# a78-flashcart.net
KiCad netlist of a schematic drawn in EAGLE
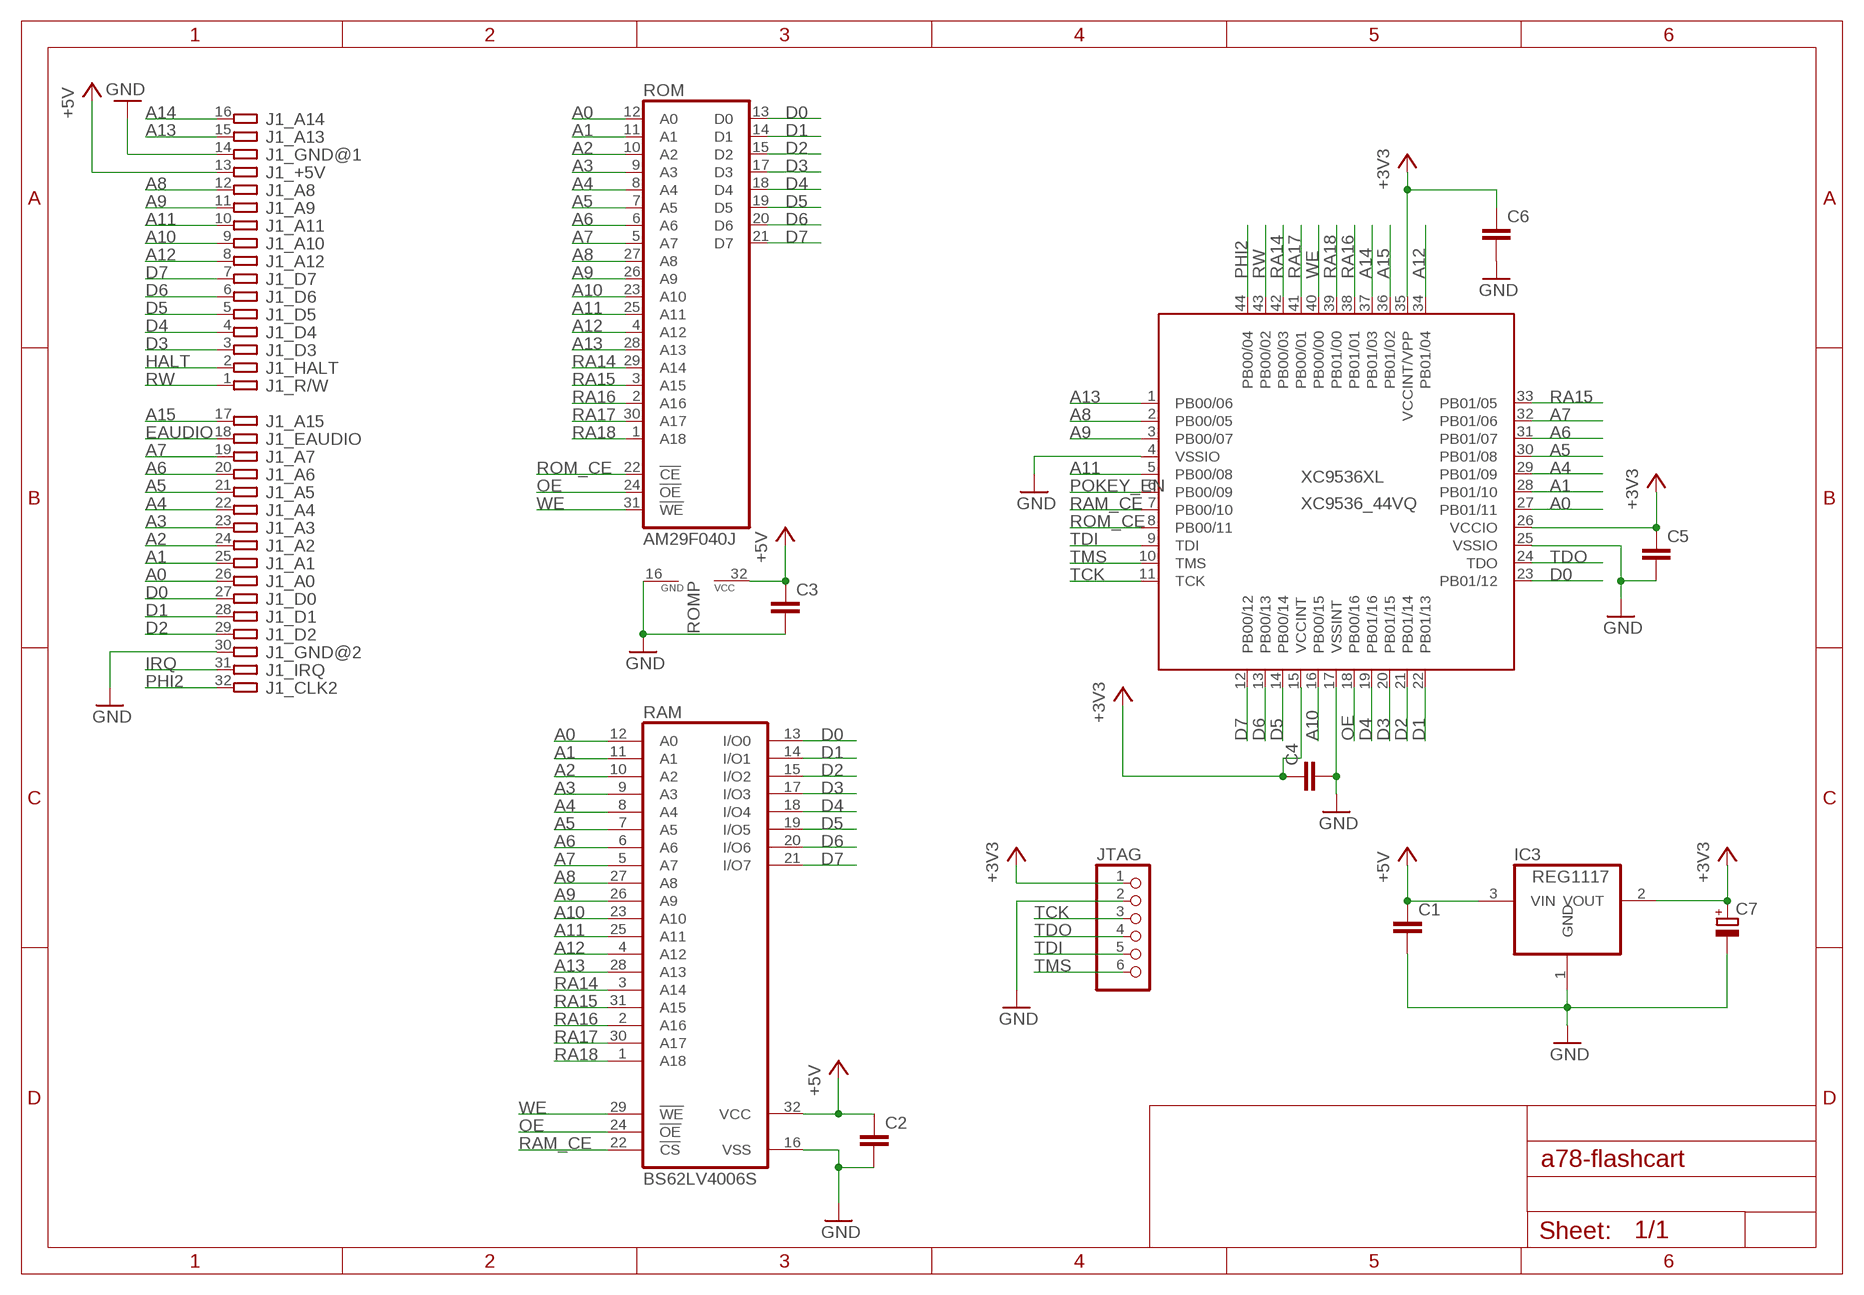
[diagram p0: schematic, sheet 1]

(export (version "E")
  (design (tool "Eeschema 10.0.6"))
  (components
    (comp (ref "C1")
      (value "C-EUC0603")
      (footprint "eagle-import:C0603")
      (libsource (lib "eagle-import") (part "C-EUC0603"))
    )
    (comp (ref "C2")
      (value "C-EUC0603")
      (footprint "eagle-import:C0603")
      (libsource (lib "eagle-import") (part "C-EUC0603"))
    )
    (comp (ref "C3")
      (value "C-EUC0603")
      (footprint "eagle-import:C0603")
      (libsource (lib "eagle-import") (part "C-EUC0603"))
    )
    (comp (ref "C4")
      (value "C-EUC0603")
      (footprint "eagle-import:C0603")
      (libsource (lib "eagle-import") (part "C-EUC0603"))
    )
    (comp (ref "C5")
      (value "C-EUC0603")
      (footprint "eagle-import:C0603")
      (libsource (lib "eagle-import") (part "C-EUC0603"))
    )
    (comp (ref "C6")
      (value "C-EUC0603")
      (footprint "eagle-import:C0603")
      (libsource (lib "eagle-import") (part "C-EUC0603"))
    )
    (comp (ref "C7")
      (value "CPOL-EUSMCC")
      (footprint "eagle-import:SMC_C")
      (libsource (lib "eagle-import") (part "CPOL-EUSMCC"))
    )
    (comp (ref "IC3")
      (value "REG1117")
      (footprint "eagle-import:SOT223")
      (libsource (lib "eagle-import") (part "REG1117"))
    )
    (comp (ref "J1")
      (value "ATARI-7800-SMALL")
      (footprint "eagle-import:ATARI-7800-SMALL")
      (libsource (lib "eagle-import") (part "ATARI-7800-SMALL"))
    )
    (comp (ref "JTAG")
      (value "PINHD-1X6")
      (footprint "eagle-import:1X06")
      (libsource (lib "eagle-import") (part "PINHD-1X6"))
    )
    (comp (ref "RAM")
      (value "BS62LV4006S")
      (footprint "eagle-import:SOP-32")
      (libsource (lib "eagle-import") (part "BS62LV4006S"))
    )
    (comp (ref "ROM")
      (value "AM29F040J")
      (footprint "eagle-import:PLCC32R")
      (libsource (lib "eagle-import") (part "AM29F040J"))
    )
    (comp (ref "XC9536XL")
      (value "XC9536_44VQ")
      (footprint "eagle-import:SQFP-S-10X10-44")
      (fields (field (name "MPN") "XC9536-15VQG44C"))
      (libsource (lib "eagle-import") (part "XC9536_44VQ"))
    )
  )
  (nets
    (net (code "1") (name "+3V3") (class "Default")
      (node (ref "C4") (pin "1") (pinfunction "1_1") (pintype "passive"))
      (node (ref "C5") (pin "1") (pinfunction "1_1") (pintype "passive"))
      (node (ref "C6") (pin "1") (pinfunction "1_1") (pintype "passive"))
      (node (ref "C7") (pin "+") (pinfunction "+_+") (pintype "passive"))
      (node (ref "IC3") (pin "2") (pinfunction "VOUT_2") (pintype "output"))
      (node (ref "JTAG") (pin "1") (pinfunction "1_1") (pintype "passive"))
      (node (ref "XC9536XL") (pin "15") (pinfunction "VCCINT_15") (pintype "power_in"))
      (node (ref "XC9536XL") (pin "26") (pinfunction "VCCIO_26") (pintype "power_in"))
      (node (ref "XC9536XL") (pin "35") (pinfunction "VCCINT/VPP_35") (pintype "input"))
    )
    (net (code "2") (name "+5V") (class "Default")
      (node (ref "C1") (pin "1") (pinfunction "1_1") (pintype "passive"))
      (node (ref "C2") (pin "1") (pinfunction "1_1") (pintype "passive"))
      (node (ref "C3") (pin "1") (pinfunction "1_1") (pintype "passive"))
      (node (ref "IC3") (pin "3") (pinfunction "VIN_3") (pintype "input"))
      (node (ref "J1") (pin "13") (pinfunction "P_13") (pintype "bidirectional"))
      (node (ref "RAM") (pin "32") (pinfunction "VCC_32") (pintype "power_in"))
      (node (ref "ROM") (pin "32") (pinfunction "VCC_32") (pintype "power_in"))
    )
    (net (code "3") (name "/A0") (class "Default")
      (node (ref "J1") (pin "26") (pinfunction "P_26") (pintype "bidirectional"))
      (node (ref "RAM") (pin "12") (pinfunction "A0_12") (pintype "input"))
      (node (ref "ROM") (pin "12") (pinfunction "A0_12") (pintype "input"))
      (node (ref "XC9536XL") (pin "27") (pinfunction "PB01/11_27") (pintype "bidirectional"))
    )
    (net (code "4") (name "/A1") (class "Default")
      (node (ref "J1") (pin "25") (pinfunction "P_25") (pintype "bidirectional"))
      (node (ref "RAM") (pin "11") (pinfunction "A1_11") (pintype "input"))
      (node (ref "ROM") (pin "11") (pinfunction "A1_11") (pintype "input"))
      (node (ref "XC9536XL") (pin "28") (pinfunction "PB01/10_28") (pintype "bidirectional"))
    )
    (net (code "5") (name "/A2") (class "Default")
      (node (ref "J1") (pin "24") (pinfunction "P_24") (pintype "bidirectional"))
      (node (ref "RAM") (pin "10") (pinfunction "A2_10") (pintype "input"))
      (node (ref "ROM") (pin "10") (pinfunction "A2_10") (pintype "input"))
    )
    (net (code "6") (name "/A3") (class "Default")
      (node (ref "J1") (pin "23") (pinfunction "P_23") (pintype "bidirectional"))
      (node (ref "RAM") (pin "9") (pinfunction "A3_9") (pintype "input"))
      (node (ref "ROM") (pin "9") (pinfunction "A3_9") (pintype "input"))
    )
    (net (code "7") (name "/A4") (class "Default")
      (node (ref "J1") (pin "22") (pinfunction "P_22") (pintype "bidirectional"))
      (node (ref "RAM") (pin "8") (pinfunction "A4_8") (pintype "input"))
      (node (ref "ROM") (pin "8") (pinfunction "A4_8") (pintype "input"))
      (node (ref "XC9536XL") (pin "29") (pinfunction "PB01/09_29") (pintype "bidirectional"))
    )
    (net (code "8") (name "/A5") (class "Default")
      (node (ref "J1") (pin "21") (pinfunction "P_21") (pintype "bidirectional"))
      (node (ref "RAM") (pin "7") (pinfunction "A5_7") (pintype "input"))
      (node (ref "ROM") (pin "7") (pinfunction "A5_7") (pintype "input"))
      (node (ref "XC9536XL") (pin "30") (pinfunction "PB01/08_30") (pintype "bidirectional"))
    )
    (net (code "9") (name "/A6") (class "Default")
      (node (ref "J1") (pin "20") (pinfunction "P_20") (pintype "bidirectional"))
      (node (ref "RAM") (pin "6") (pinfunction "A6_6") (pintype "input"))
      (node (ref "ROM") (pin "6") (pinfunction "A6_6") (pintype "input"))
      (node (ref "XC9536XL") (pin "31") (pinfunction "PB01/07_31") (pintype "bidirectional"))
    )
    (net (code "10") (name "/A7") (class "Default")
      (node (ref "J1") (pin "19") (pinfunction "P_19") (pintype "bidirectional"))
      (node (ref "RAM") (pin "5") (pinfunction "A7_5") (pintype "input"))
      (node (ref "ROM") (pin "5") (pinfunction "A7_5") (pintype "input"))
      (node (ref "XC9536XL") (pin "32") (pinfunction "PB01/06_32") (pintype "bidirectional"))
    )
    (net (code "11") (name "/A8") (class "Default")
      (node (ref "J1") (pin "12") (pinfunction "P_12") (pintype "bidirectional"))
      (node (ref "RAM") (pin "27") (pinfunction "A8_27") (pintype "input"))
      (node (ref "ROM") (pin "27") (pinfunction "A8_27") (pintype "input"))
      (node (ref "XC9536XL") (pin "2") (pinfunction "PB00/05_2") (pintype "bidirectional"))
    )
    (net (code "12") (name "/A9") (class "Default")
      (node (ref "J1") (pin "11") (pinfunction "P_11") (pintype "bidirectional"))
      (node (ref "RAM") (pin "26") (pinfunction "A9_26") (pintype "input"))
      (node (ref "ROM") (pin "26") (pinfunction "A9_26") (pintype "input"))
      (node (ref "XC9536XL") (pin "3") (pinfunction "PB00/07_3") (pintype "bidirectional"))
    )
    (net (code "13") (name "/A10") (class "Default")
      (node (ref "J1") (pin "9") (pinfunction "P_9") (pintype "bidirectional"))
      (node (ref "RAM") (pin "23") (pinfunction "A10_23") (pintype "input"))
      (node (ref "ROM") (pin "23") (pinfunction "A10_23") (pintype "input"))
      (node (ref "XC9536XL") (pin "16") (pinfunction "PB00/15_16") (pintype "bidirectional"))
    )
    (net (code "14") (name "/A11") (class "Default")
      (node (ref "J1") (pin "10") (pinfunction "P_10") (pintype "bidirectional"))
      (node (ref "RAM") (pin "25") (pinfunction "A11_25") (pintype "input"))
      (node (ref "ROM") (pin "25") (pinfunction "A11_25") (pintype "input"))
      (node (ref "XC9536XL") (pin "5") (pinfunction "PB00/08_5") (pintype "bidirectional"))
    )
    (net (code "15") (name "/A12") (class "Default")
      (node (ref "J1") (pin "8") (pinfunction "P_8") (pintype "bidirectional"))
      (node (ref "RAM") (pin "4") (pinfunction "A12_4") (pintype "input"))
      (node (ref "ROM") (pin "4") (pinfunction "A12_4") (pintype "input"))
      (node (ref "XC9536XL") (pin "34") (pinfunction "PB01/04_34") (pintype "bidirectional"))
    )
    (net (code "16") (name "/A13") (class "Default")
      (node (ref "J1") (pin "15") (pinfunction "P_15") (pintype "bidirectional"))
      (node (ref "RAM") (pin "28") (pinfunction "A13_28") (pintype "input"))
      (node (ref "ROM") (pin "28") (pinfunction "A13_28") (pintype "input"))
      (node (ref "XC9536XL") (pin "1") (pinfunction "PB00/06_1") (pintype "bidirectional"))
    )
    (net (code "17") (name "/A14") (class "Default")
      (node (ref "J1") (pin "16") (pinfunction "P_16") (pintype "bidirectional"))
      (node (ref "XC9536XL") (pin "37") (pinfunction "PB01/03_37") (pintype "bidirectional"))
    )
    (net (code "18") (name "/A15") (class "Default")
      (node (ref "J1") (pin "17") (pinfunction "P_17") (pintype "bidirectional"))
      (node (ref "XC9536XL") (pin "36") (pinfunction "PB01/02_36") (pintype "bidirectional"))
    )
    (net (code "19") (name "/D0") (class "Default")
      (node (ref "J1") (pin "27") (pinfunction "P_27") (pintype "bidirectional"))
      (node (ref "RAM") (pin "13") (pinfunction "I/O0_13") (pintype "bidirectional"))
      (node (ref "ROM") (pin "13") (pinfunction "D0_13") (pintype "tri_state"))
      (node (ref "XC9536XL") (pin "23") (pinfunction "PB01/12_23") (pintype "bidirectional"))
    )
    (net (code "20") (name "/D1") (class "Default")
      (node (ref "J1") (pin "28") (pinfunction "P_28") (pintype "bidirectional"))
      (node (ref "RAM") (pin "14") (pinfunction "I/O1_14") (pintype "bidirectional"))
      (node (ref "ROM") (pin "14") (pinfunction "D1_14") (pintype "tri_state"))
      (node (ref "XC9536XL") (pin "22") (pinfunction "PB01/13_22") (pintype "bidirectional"))
    )
    (net (code "21") (name "/D2") (class "Default")
      (node (ref "J1") (pin "29") (pinfunction "P_29") (pintype "bidirectional"))
      (node (ref "RAM") (pin "15") (pinfunction "I/O2_15") (pintype "bidirectional"))
      (node (ref "ROM") (pin "15") (pinfunction "D2_15") (pintype "tri_state"))
      (node (ref "XC9536XL") (pin "21") (pinfunction "PB01/14_21") (pintype "bidirectional"))
    )
    (net (code "22") (name "/D3") (class "Default")
      (node (ref "J1") (pin "3") (pinfunction "P_3") (pintype "bidirectional"))
      (node (ref "RAM") (pin "17") (pinfunction "I/O3_17") (pintype "bidirectional"))
      (node (ref "ROM") (pin "17") (pinfunction "D3_17") (pintype "tri_state"))
      (node (ref "XC9536XL") (pin "20") (pinfunction "PB01/15_20") (pintype "bidirectional"))
    )
    (net (code "23") (name "/D4") (class "Default")
      (node (ref "J1") (pin "4") (pinfunction "P_4") (pintype "bidirectional"))
      (node (ref "RAM") (pin "18") (pinfunction "I/O4_18") (pintype "bidirectional"))
      (node (ref "ROM") (pin "18") (pinfunction "D4_18") (pintype "tri_state"))
      (node (ref "XC9536XL") (pin "19") (pinfunction "PB01/16_19") (pintype "bidirectional"))
    )
    (net (code "24") (name "/D5") (class "Default")
      (node (ref "J1") (pin "5") (pinfunction "P_5") (pintype "bidirectional"))
      (node (ref "RAM") (pin "19") (pinfunction "I/O5_19") (pintype "bidirectional"))
      (node (ref "ROM") (pin "19") (pinfunction "D5_19") (pintype "tri_state"))
      (node (ref "XC9536XL") (pin "14") (pinfunction "PB00/14_14") (pintype "bidirectional"))
    )
    (net (code "25") (name "/D6") (class "Default")
      (node (ref "J1") (pin "6") (pinfunction "P_6") (pintype "bidirectional"))
      (node (ref "RAM") (pin "20") (pinfunction "I/O6_20") (pintype "bidirectional"))
      (node (ref "ROM") (pin "20") (pinfunction "D6_20") (pintype "tri_state"))
      (node (ref "XC9536XL") (pin "13") (pinfunction "PB00/13_13") (pintype "bidirectional"))
    )
    (net (code "26") (name "/D7") (class "Default")
      (node (ref "J1") (pin "7") (pinfunction "P_7") (pintype "bidirectional"))
      (node (ref "RAM") (pin "21") (pinfunction "I/O7_21") (pintype "bidirectional"))
      (node (ref "ROM") (pin "21") (pinfunction "D7_21") (pintype "tri_state"))
      (node (ref "XC9536XL") (pin "12") (pinfunction "PB00/12_12") (pintype "bidirectional"))
    )
    (net (code "27") (name "/EAUDIO") (class "Default")
      (node (ref "J1") (pin "18") (pinfunction "P_18") (pintype "bidirectional"))
    )
    (net (code "28") (name "/HALT") (class "Default")
      (node (ref "J1") (pin "2") (pinfunction "P_2") (pintype "bidirectional"))
    )
    (net (code "29") (name "/IRQ") (class "Default")
      (node (ref "J1") (pin "31") (pinfunction "P_31") (pintype "bidirectional"))
    )
    (net (code "30") (name "/OE") (class "Default")
      (node (ref "RAM") (pin "24") (pinfunction "~{OE}_24") (pintype "input"))
      (node (ref "ROM") (pin "24") (pinfunction "~{OE}_24") (pintype "input"))
      (node (ref "XC9536XL") (pin "18") (pinfunction "PB00/16_18") (pintype "bidirectional"))
    )
    (net (code "31") (name "/PHI2") (class "Default")
      (node (ref "J1") (pin "32") (pinfunction "P_32") (pintype "bidirectional"))
      (node (ref "XC9536XL") (pin "44") (pinfunction "PB00/04_44") (pintype "bidirectional"))
    )
    (net (code "32") (name "/POKEY_EN") (class "Default")
      (node (ref "XC9536XL") (pin "6") (pinfunction "PB00/09_6") (pintype "bidirectional"))
    )
    (net (code "33") (name "/RA14") (class "Default")
      (node (ref "RAM") (pin "3") (pinfunction "A14_3") (pintype "input"))
      (node (ref "ROM") (pin "29") (pinfunction "A14_29") (pintype "input"))
      (node (ref "XC9536XL") (pin "42") (pinfunction "PB00/03_42") (pintype "bidirectional"))
    )
    (net (code "34") (name "/RA15") (class "Default")
      (node (ref "RAM") (pin "31") (pinfunction "A15_31") (pintype "input"))
      (node (ref "ROM") (pin "3") (pinfunction "A15_3") (pintype "input"))
      (node (ref "XC9536XL") (pin "33") (pinfunction "PB01/05_33") (pintype "bidirectional"))
    )
    (net (code "35") (name "/RA16") (class "Default")
      (node (ref "RAM") (pin "2") (pinfunction "A16_2") (pintype "input"))
      (node (ref "ROM") (pin "2") (pinfunction "A16_2") (pintype "input"))
      (node (ref "XC9536XL") (pin "38") (pinfunction "PB01/01_38") (pintype "bidirectional"))
    )
    (net (code "36") (name "/RA17") (class "Default")
      (node (ref "RAM") (pin "30") (pinfunction "A17_30") (pintype "input"))
      (node (ref "ROM") (pin "30") (pinfunction "A17_30") (pintype "input"))
      (node (ref "XC9536XL") (pin "41") (pinfunction "PB00/01_41") (pintype "bidirectional"))
    )
    (net (code "37") (name "/RA18") (class "Default")
      (node (ref "RAM") (pin "1") (pinfunction "A18_1") (pintype "input"))
      (node (ref "ROM") (pin "1") (pinfunction "A18_1") (pintype "input"))
      (node (ref "XC9536XL") (pin "39") (pinfunction "PB01/00_39") (pintype "bidirectional"))
    )
    (net (code "38") (name "/RAM_CE") (class "Default")
      (node (ref "RAM") (pin "22") (pinfunction "~{CS}_22") (pintype "input"))
      (node (ref "XC9536XL") (pin "7") (pinfunction "PB00/10_7") (pintype "bidirectional"))
    )
    (net (code "39") (name "/ROM_CE") (class "Default")
      (node (ref "ROM") (pin "22") (pinfunction "~{CE}_22") (pintype "input"))
      (node (ref "XC9536XL") (pin "8") (pinfunction "PB00/11_8") (pintype "bidirectional"))
    )
    (net (code "40") (name "/RW") (class "Default")
      (node (ref "J1") (pin "1") (pinfunction "P_1") (pintype "bidirectional"))
      (node (ref "XC9536XL") (pin "43") (pinfunction "PB00/02_43") (pintype "bidirectional"))
    )
    (net (code "41") (name "/TCK") (class "Default")
      (node (ref "JTAG") (pin "3") (pinfunction "3_3") (pintype "passive"))
      (node (ref "XC9536XL") (pin "11") (pinfunction "TCK_11") (pintype "input"))
    )
    (net (code "42") (name "/TDI") (class "Default")
      (node (ref "JTAG") (pin "5") (pinfunction "5_5") (pintype "passive"))
      (node (ref "XC9536XL") (pin "9") (pinfunction "TDI_9") (pintype "input"))
    )
    (net (code "43") (name "/TDO") (class "Default")
      (node (ref "JTAG") (pin "4") (pinfunction "4_4") (pintype "passive"))
      (node (ref "XC9536XL") (pin "24") (pinfunction "TDO_24") (pintype "output"))
    )
    (net (code "44") (name "/TMS") (class "Default")
      (node (ref "JTAG") (pin "6") (pinfunction "6_6") (pintype "passive"))
      (node (ref "XC9536XL") (pin "10") (pinfunction "TMS_10") (pintype "input"))
    )
    (net (code "45") (name "/WE") (class "Default")
      (node (ref "RAM") (pin "29") (pinfunction "~{WE}_29") (pintype "input"))
      (node (ref "ROM") (pin "31") (pinfunction "~{WE}_31") (pintype "input"))
      (node (ref "XC9536XL") (pin "40") (pinfunction "PB00/00_40") (pintype "bidirectional"))
    )
    (net (code "46") (name "GND") (class "Default")
      (node (ref "C1") (pin "2") (pinfunction "2_2") (pintype "passive"))
      (node (ref "C2") (pin "2") (pinfunction "2_2") (pintype "passive"))
      (node (ref "C3") (pin "2") (pinfunction "2_2") (pintype "passive"))
      (node (ref "C4") (pin "2") (pinfunction "2_2") (pintype "passive"))
      (node (ref "C5") (pin "2") (pinfunction "2_2") (pintype "passive"))
      (node (ref "C6") (pin "2") (pinfunction "2_2") (pintype "passive"))
      (node (ref "C7") (pin "-") (pinfunction "-_-") (pintype "passive"))
      (node (ref "IC3") (pin "1") (pinfunction "GND_1") (pintype "power_in"))
      (node (ref "J1") (pin "14") (pinfunction "P_14") (pintype "bidirectional"))
      (node (ref "J1") (pin "30") (pinfunction "P_30") (pintype "bidirectional"))
      (node (ref "JTAG") (pin "2") (pinfunction "2_2") (pintype "passive"))
      (node (ref "RAM") (pin "16") (pinfunction "VSS_16") (pintype "power_in"))
      (node (ref "ROM") (pin "16") (pinfunction "GND_16") (pintype "power_in"))
      (node (ref "XC9536XL") (pin "17") (pinfunction "VSSINT_17") (pintype "power_in"))
      (node (ref "XC9536XL") (pin "25") (pinfunction "VSSIO_25") (pintype "power_in"))
      (node (ref "XC9536XL") (pin "4") (pinfunction "VSSIO_4") (pintype "power_in"))
    )
  )
)
